# DAC_8CH.net
KiCad netlist of a schematic drawn in Altium Designer
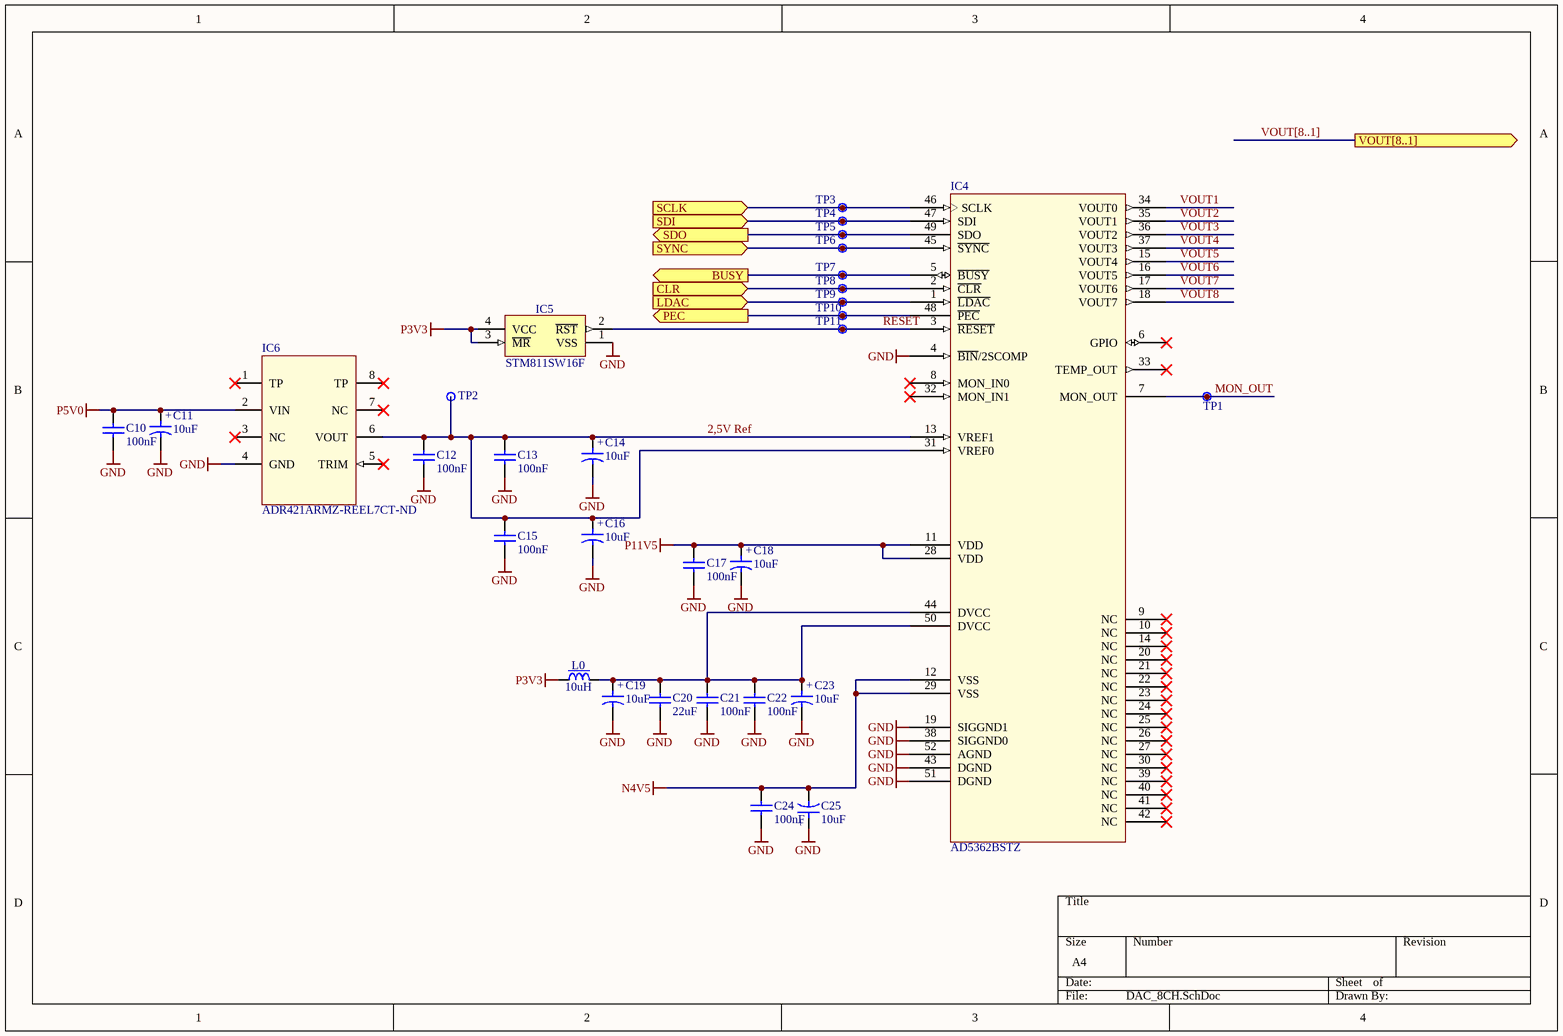
[diagram p0: DAC_8CH.SchDoc]

(export (version "E")
  (design (tool "Eeschema 10.0.6"))
  (components
    (comp (ref "C10")
      (value "100nF")
      (footprint "C0402C104K4RACTU")
      (description "Capacitor; Ceramic; Cap; .100uF; Tol 10%; SMT; Vol-Rtg 16V; X7R; Tape and Reel")
      (fields (field (name "TOLERANCE") "10%"))
      (libsource (lib "CapacitorLibrary") (part "C0402C104K4RACTU"))
    )
    (comp (ref "C11")
      (value "10uF")
      (footprint "TCJT106M016R0200")
      (description "CAP TANT POLY 10UF 16V 1210")
      (fields (field (name "TOLERANCE") "20%") (field (name "VOLTAGE") "16V"))
      (libsource (lib "CapacitorLibrary") (part "TCJT106M016R0200"))
    )
    (comp (ref "C12")
      (value "100nF")
      (footprint "C0402C104K4RACTU")
      (description "Capacitor; Ceramic; Cap; .100uF; Tol 10%; SMT; Vol-Rtg 16V; X7R; Tape and Reel")
      (fields (field (name "TOLERANCE") "10%"))
      (libsource (lib "CapacitorLibrary") (part "C0402C104K4RACTU"))
    )
    (comp (ref "C13")
      (value "100nF")
      (footprint "C0402C104K4RACTU")
      (description "Capacitor; Ceramic; Cap; .100uF; Tol 10%; SMT; Vol-Rtg 16V; X7R; Tape and Reel")
      (fields (field (name "TOLERANCE") "10%"))
      (libsource (lib "CapacitorLibrary") (part "C0402C104K4RACTU"))
    )
    (comp (ref "C14")
      (value "10uF")
      (footprint "TCJT106M016R0200")
      (description "CAP TANT POLY 10UF 16V 1210")
      (fields (field (name "TOLERANCE") "20%") (field (name "VOLTAGE") "16V"))
      (libsource (lib "CapacitorLibrary") (part "TCJT106M016R0200"))
    )
    (comp (ref "C15")
      (value "100nF")
      (footprint "C0402C104K4RACTU")
      (description "Capacitor; Ceramic; Cap; .100uF; Tol 10%; SMT; Vol-Rtg 16V; X7R; Tape and Reel")
      (fields (field (name "TOLERANCE") "10%"))
      (libsource (lib "CapacitorLibrary") (part "C0402C104K4RACTU"))
    )
    (comp (ref "C16")
      (value "10uF")
      (footprint "TCJT106M016R0200")
      (description "CAP TANT POLY 10UF 16V 1210")
      (fields (field (name "TOLERANCE") "20%") (field (name "VOLTAGE") "16V"))
      (libsource (lib "CapacitorLibrary") (part "TCJT106M016R0200"))
    )
    (comp (ref "C17")
      (value "100nF")
      (footprint "C0402C104K4RACTU")
      (description "Capacitor; Ceramic; Cap; .100uF; Tol 10%; SMT; Vol-Rtg 16V; X7R; Tape and Reel")
      (fields (field (name "TOLERANCE") "10%"))
      (libsource (lib "CapacitorLibrary") (part "C0402C104K4RACTU"))
    )
    (comp (ref "C18")
      (value "10uF")
      (footprint "TCJT106M016R0200")
      (description "CAP TANT POLY 10UF 16V 1210")
      (fields (field (name "TOLERANCE") "20%") (field (name "VOLTAGE") "16V"))
      (libsource (lib "CapacitorLibrary") (part "TCJT106M016R0200"))
    )
    (comp (ref "C19")
      (value "10uF")
      (footprint "TCJT106M016R0200")
      (description "CAP TANT POLY 10UF 16V 1210")
      (fields (field (name "TOLERANCE") "20%") (field (name "VOLTAGE") "16V"))
      (libsource (lib "CapacitorLibrary") (part "TCJT106M016R0200"))
    )
    (comp (ref "C20")
      (value "22uF")
      (footprint "GRM219R61C226ME15K")
      (description "CAP CER 22uF 16V X5R 20% SMD 0805 85°C Embossed T/R")
      (fields (field (name "TOLERANCE") "20%"))
      (libsource (lib "CapacitorLibrary") (part "GRM219R61C226ME15K"))
    )
    (comp (ref "C21")
      (value "100nF")
      (footprint "C0402C104K4RACTU")
      (description "Capacitor; Ceramic; Cap; .100uF; Tol 10%; SMT; Vol-Rtg 16V; X7R; Tape and Reel")
      (fields (field (name "TOLERANCE") "10%"))
      (libsource (lib "CapacitorLibrary") (part "C0402C104K4RACTU"))
    )
    (comp (ref "C22")
      (value "100nF")
      (footprint "C0402C104K4RACTU")
      (description "Capacitor; Ceramic; Cap; .100uF; Tol 10%; SMT; Vol-Rtg 16V; X7R; Tape and Reel")
      (fields (field (name "TOLERANCE") "10%"))
      (libsource (lib "CapacitorLibrary") (part "C0402C104K4RACTU"))
    )
    (comp (ref "C23")
      (value "10uF")
      (footprint "TCJT106M016R0200")
      (description "CAP TANT POLY 10UF 16V 1210")
      (fields (field (name "TOLERANCE") "20%") (field (name "VOLTAGE") "16V"))
      (libsource (lib "CapacitorLibrary") (part "TCJT106M016R0200"))
    )
    (comp (ref "C24")
      (value "100nF")
      (footprint "C0402C104K4RACTU")
      (description "Capacitor; Ceramic; Cap; .100uF; Tol 10%; SMT; Vol-Rtg 16V; X7R; Tape and Reel")
      (fields (field (name "TOLERANCE") "10%"))
      (libsource (lib "CapacitorLibrary") (part "C0402C104K4RACTU"))
    )
    (comp (ref "C25")
      (value "10uF")
      (footprint "TCJT106M016R0200")
      (description "CAP TANT POLY 10UF 16V 1210")
      (fields (field (name "TOLERANCE") "20%") (field (name "VOLTAGE") "16V"))
      (libsource (lib "CapacitorLibrary") (part "TCJT106M016R0200"))
    )
    (comp (ref "IC4")
      (value "AD5362BSTZ")
      (footprint "ST-52_L")
      (description "IC, 16BIT DAC, 8CH, SERIAL, 52LFCSP")
      (libsource (lib "InzLib") (part "AD5362BSTZ"))
    )
    (comp (ref "IC5")
      (value "STM811SW16F")
      (footprint "SOT143N")
      (description "Microprocessor Reset Circuit")
      (fields (field (name "MANUFACTURER") "ST MICROELECTRONICS") (field (name "AUTHOR") "CERN DEM JLC"))
      (libsource (lib "ICs And Semiconductors") (part "STM811"))
    )
    (comp (ref "IC6")
      (value "ADR421ARMZ-REEL7")
      (footprint "ADI-RM-8_N")
      (description "V-Ref Precision 2.5V 10mA 8-Pin MSOP T/R")
      (fields
        (field (name "TOLERANCE") "0.12%")
        (field (name "SUPPLIER PART NUMBER 1") "ADR421ARMZ-REEL7CT-ND")
      )
      (libsource (lib "InzLib") (part "ADR421ARMZ-REEL7"))
    )
    (comp (ref "L0")
      (value "10uH")
      (footprint "IND_MURATA-PS_8400")
      (description "Inductor With Core")
      (fields
        (field (name "PART NUMBER") "IND_10UH_10%_MURATA-PS_8400")
        (field (name "POWER") "950mA")
        (field (name "AUTHOR") "CERN DEM JLC")
      )
      (libsource (lib "Inductors & Transformers") (part "Inductor With Magnetic core"))
    )
    (comp (ref "TP1")
      (value "Test Point")
      (footprint "TPS127")
      (fields (field (name "PART NUMBER") "SMD_PAD_1.27X1.27MM") (field (name "AUTHOR") "CERN DEM JLC"))
      (libsource (lib "Eletro-mechanical") (part "Test Point"))
    )
    (comp (ref "TP2")
      (value "Test Point")
      (footprint "TPS127")
      (fields (field (name "PART NUMBER") "SMD_PAD_1.27X1.27MM") (field (name "AUTHOR") "CERN DEM JLC"))
      (libsource (lib "Eletro-mechanical") (part "Test Point"))
    )
    (comp (ref "TP3")
      (value "Test Point")
      (footprint "TPS127")
      (fields (field (name "PART NUMBER") "SMD_PAD_1.27X1.27MM") (field (name "AUTHOR") "CERN DEM JLC"))
      (libsource (lib "Eletro-mechanical") (part "Test Point"))
    )
    (comp (ref "TP4")
      (value "Test Point")
      (footprint "TPS127")
      (fields (field (name "PART NUMBER") "SMD_PAD_1.27X1.27MM") (field (name "AUTHOR") "CERN DEM JLC"))
      (libsource (lib "Eletro-mechanical") (part "Test Point"))
    )
    (comp (ref "TP5")
      (value "Test Point")
      (footprint "TPS127")
      (fields (field (name "PART NUMBER") "SMD_PAD_1.27X1.27MM") (field (name "AUTHOR") "CERN DEM JLC"))
      (libsource (lib "Eletro-mechanical") (part "Test Point"))
    )
    (comp (ref "TP6")
      (value "Test Point")
      (footprint "TPS127")
      (fields (field (name "PART NUMBER") "SMD_PAD_1.27X1.27MM") (field (name "AUTHOR") "CERN DEM JLC"))
      (libsource (lib "Eletro-mechanical") (part "Test Point"))
    )
    (comp (ref "TP7")
      (value "Test Point")
      (footprint "TPS127")
      (fields (field (name "PART NUMBER") "SMD_PAD_1.27X1.27MM") (field (name "AUTHOR") "CERN DEM JLC"))
      (libsource (lib "Eletro-mechanical") (part "Test Point"))
    )
    (comp (ref "TP8")
      (value "Test Point")
      (footprint "TPS127")
      (fields (field (name "PART NUMBER") "SMD_PAD_1.27X1.27MM") (field (name "AUTHOR") "CERN DEM JLC"))
      (libsource (lib "Eletro-mechanical") (part "Test Point"))
    )
    (comp (ref "TP9")
      (value "Test Point")
      (footprint "TPS127")
      (fields (field (name "PART NUMBER") "SMD_PAD_1.27X1.27MM") (field (name "AUTHOR") "CERN DEM JLC"))
      (libsource (lib "Eletro-mechanical") (part "Test Point"))
    )
    (comp (ref "TP10")
      (value "Test Point")
      (footprint "TPS127")
      (fields (field (name "PART NUMBER") "SMD_PAD_1.27X1.27MM") (field (name "AUTHOR") "CERN DEM JLC"))
      (libsource (lib "Eletro-mechanical") (part "Test Point"))
    )
    (comp (ref "TP11")
      (value "Test Point")
      (footprint "TPS127")
      (fields (field (name "PART NUMBER") "SMD_PAD_1.27X1.27MM") (field (name "AUTHOR") "CERN DEM JLC"))
      (libsource (lib "Eletro-mechanical") (part "Test Point"))
    )
  )
  (nets
    (net (code "1") (name "/2,5V Ref") (class "Default")
      (node (ref "C12") (pin "2") (pinfunction "2_2") (pintype "passive"))
      (node (ref "C13") (pin "2") (pinfunction "2_2") (pintype "passive"))
      (node (ref "C14") (pin "1") (pinfunction "1_1") (pintype "passive"))
      (node (ref "C15") (pin "2") (pinfunction "2_2") (pintype "passive"))
      (node (ref "C16") (pin "1") (pinfunction "1_1") (pintype "passive"))
      (node (ref "IC4") (pin "13") (pinfunction "VREF1_13") (pintype "input"))
      (node (ref "IC4") (pin "31") (pinfunction "VREF0_31") (pintype "input"))
      (node (ref "IC6") (pin "6") (pinfunction "VOUT_6") (pintype "power_in"))
      (node (ref "TP2") (pin "1") (pinfunction "1_1") (pintype "bidirectional"))
    )
    (net (code "2") (name "/BUSY") (class "Default")
      (node (ref "IC4") (pin "5") (pinfunction "~{BUSY}_5") (pintype "bidirectional"))
      (node (ref "TP7") (pin "1") (pinfunction "1_1") (pintype "bidirectional"))
    )
    (net (code "3") (name "/CLR") (class "Default")
      (node (ref "IC4") (pin "2") (pinfunction "~{CLR}_2") (pintype "input"))
      (node (ref "TP8") (pin "1") (pinfunction "1_1") (pintype "bidirectional"))
    )
    (net (code "4") (name "/LDAC") (class "Default")
      (node (ref "IC4") (pin "1") (pinfunction "~{LDAC}_1") (pintype "input"))
      (node (ref "TP9") (pin "1") (pinfunction "1_1") (pintype "bidirectional"))
    )
    (net (code "5") (name "/MON_OUT") (class "Default")
      (node (ref "IC4") (pin "7") (pinfunction "MON_OUT_7") (pintype "tri_state"))
      (node (ref "TP1") (pin "1") (pinfunction "1_1") (pintype "bidirectional"))
    )
    (net (code "6") (name "/PEC") (class "Default")
      (node (ref "IC4") (pin "48") (pinfunction "~{PEC}_48") (pintype "open_collector"))
      (node (ref "TP10") (pin "1") (pinfunction "1_1") (pintype "bidirectional"))
    )
    (net (code "7") (name "/SCLK") (class "Default")
      (node (ref "IC4") (pin "46") (pinfunction "SCLK_46") (pintype "input"))
      (node (ref "TP3") (pin "1") (pinfunction "1_1") (pintype "bidirectional"))
    )
    (net (code "8") (name "/SDI") (class "Default")
      (node (ref "IC4") (pin "47") (pinfunction "SDI_47") (pintype "input"))
      (node (ref "TP4") (pin "1") (pinfunction "1_1") (pintype "bidirectional"))
    )
    (net (code "9") (name "/SDO") (class "Default")
      (node (ref "IC4") (pin "49") (pinfunction "SDO_49") (pintype "tri_state"))
      (node (ref "TP5") (pin "1") (pinfunction "1_1") (pintype "bidirectional"))
    )
    (net (code "10") (name "/SYNC") (class "Default")
      (node (ref "IC4") (pin "45") (pinfunction "~{SYNC}_45") (pintype "input"))
      (node (ref "TP6") (pin "1") (pinfunction "1_1") (pintype "bidirectional"))
    )
    (net (code "11") (name "/VOUT1") (class "Default")
      (node (ref "IC4") (pin "34") (pinfunction "VOUT0_34") (pintype "output"))
    )
    (net (code "12") (name "/VOUT2") (class "Default")
      (node (ref "IC4") (pin "35") (pinfunction "VOUT1_35") (pintype "output"))
    )
    (net (code "13") (name "/VOUT3") (class "Default")
      (node (ref "IC4") (pin "36") (pinfunction "VOUT2_36") (pintype "output"))
    )
    (net (code "14") (name "/VOUT4") (class "Default")
      (node (ref "IC4") (pin "37") (pinfunction "VOUT3_37") (pintype "output"))
    )
    (net (code "15") (name "/VOUT5") (class "Default")
      (node (ref "IC4") (pin "15") (pinfunction "VOUT4_15") (pintype "output"))
    )
    (net (code "16") (name "/VOUT6") (class "Default")
      (node (ref "IC4") (pin "16") (pinfunction "VOUT5_16") (pintype "output"))
    )
    (net (code "17") (name "/VOUT7") (class "Default")
      (node (ref "IC4") (pin "17") (pinfunction "VOUT6_17") (pintype "output"))
    )
    (net (code "18") (name "/VOUT8") (class "Default")
      (node (ref "IC4") (pin "18") (pinfunction "VOUT7_18") (pintype "output"))
    )
    (net (code "20") (name "/~{RESET}") (class "Default")
      (node (ref "IC4") (pin "3") (pinfunction "~{RESET}_3") (pintype "input"))
      (node (ref "IC5") (pin "2") (pinfunction "~{RST}_2") (pintype "output"))
      (node (ref "TP11") (pin "1") (pinfunction "1_1") (pintype "bidirectional"))
    )
    (net (code "21") (name "GND") (class "Default")
      (node (ref "C10") (pin "1") (pinfunction "1_1") (pintype "passive"))
      (node (ref "C11") (pin "2") (pinfunction "2_2") (pintype "passive"))
      (node (ref "C12") (pin "1") (pinfunction "1_1") (pintype "passive"))
      (node (ref "C13") (pin "1") (pinfunction "1_1") (pintype "passive"))
      (node (ref "C14") (pin "2") (pinfunction "2_2") (pintype "passive"))
      (node (ref "C15") (pin "1") (pinfunction "1_1") (pintype "passive"))
      (node (ref "C16") (pin "2") (pinfunction "2_2") (pintype "passive"))
      (node (ref "C17") (pin "1") (pinfunction "1_1") (pintype "passive"))
      (node (ref "C18") (pin "2") (pinfunction "2_2") (pintype "passive"))
      (node (ref "C19") (pin "2") (pinfunction "2_2") (pintype "passive"))
      (node (ref "C20") (pin "1") (pinfunction "1_1") (pintype "passive"))
      (node (ref "C21") (pin "1") (pinfunction "1_1") (pintype "passive"))
      (node (ref "C22") (pin "1") (pinfunction "1_1") (pintype "passive"))
      (node (ref "C23") (pin "2") (pinfunction "2_2") (pintype "passive"))
      (node (ref "C24") (pin "1") (pinfunction "1_1") (pintype "passive"))
      (node (ref "C25") (pin "1") (pinfunction "1_1") (pintype "passive"))
      (node (ref "IC4") (pin "19") (pinfunction "SIGGND1_19") (pintype "power_in"))
      (node (ref "IC4") (pin "38") (pinfunction "SIGGND0_38") (pintype "power_in"))
      (node (ref "IC4") (pin "4") (pinfunction "~{BIN}/2SCOMP_4") (pintype "input"))
      (node (ref "IC4") (pin "43") (pinfunction "DGND_43") (pintype "power_in"))
      (node (ref "IC4") (pin "51") (pinfunction "DGND_51") (pintype "power_in"))
      (node (ref "IC4") (pin "52") (pinfunction "AGND_52") (pintype "power_in"))
      (node (ref "IC5") (pin "1") (pinfunction "VSS_1") (pintype "power_in"))
      (node (ref "IC6") (pin "4") (pinfunction "GND_4") (pintype "power_in"))
    )
    (net (code "22") (name "N4V5") (class "Default")
      (node (ref "C24") (pin "2") (pinfunction "2_2") (pintype "passive"))
      (node (ref "C25") (pin "2") (pinfunction "2_2") (pintype "passive"))
      (node (ref "IC4") (pin "12") (pinfunction "VSS_12") (pintype "power_in"))
      (node (ref "IC4") (pin "29") (pinfunction "VSS_29") (pintype "power_in"))
    )
    (net (code "23") (name "Net-(C19-Pad1)") (class "Default")
      (node (ref "C19") (pin "1") (pinfunction "1_1") (pintype "passive"))
      (node (ref "C20") (pin "2") (pinfunction "2_2") (pintype "passive"))
      (node (ref "C21") (pin "2") (pinfunction "2_2") (pintype "passive"))
      (node (ref "C22") (pin "2") (pinfunction "2_2") (pintype "passive"))
      (node (ref "C23") (pin "1") (pinfunction "1_1") (pintype "passive"))
      (node (ref "IC4") (pin "44") (pinfunction "DVCC_44") (pintype "power_in"))
      (node (ref "IC4") (pin "50") (pinfunction "DVCC_50") (pintype "power_in"))
      (node (ref "L0") (pin "2") (pinfunction "2_2") (pintype "passive"))
    )
    (net (code "24") (name "P3V3") (class "Default")
      (node (ref "IC5") (pin "3") (pinfunction "~{MR}_3") (pintype "input"))
      (node (ref "IC5") (pin "4") (pinfunction "VCC_4") (pintype "power_in"))
      (node (ref "L0") (pin "1") (pinfunction "1_1") (pintype "passive"))
    )
    (net (code "25") (name "P5V0") (class "Default")
      (node (ref "C10") (pin "2") (pinfunction "2_2") (pintype "passive"))
      (node (ref "C11") (pin "1") (pinfunction "1_1") (pintype "passive"))
      (node (ref "IC6") (pin "2") (pinfunction "VIN_2") (pintype "power_in"))
    )
    (net (code "26") (name "P11V5") (class "Default")
      (node (ref "C17") (pin "2") (pinfunction "2_2") (pintype "passive"))
      (node (ref "C18") (pin "1") (pinfunction "1_1") (pintype "passive"))
      (node (ref "IC4") (pin "11") (pinfunction "VDD_11") (pintype "power_in"))
      (node (ref "IC4") (pin "28") (pinfunction "VDD_28") (pintype "power_in"))
    )
    (net (code "27") (name "unconnected-(IC4-GPIO-Pad6)") (class "Default")
      (node (ref "IC4") (pin "6") (pinfunction "GPIO_6") (pintype "bidirectional+no_connect"))
    )
    (net (code "28") (name "unconnected-(IC4-MON_IN0-Pad8)") (class "Default")
      (node (ref "IC4") (pin "8") (pinfunction "MON_IN0_8") (pintype "input+no_connect"))
    )
    (net (code "29") (name "unconnected-(IC4-MON_IN1-Pad32)") (class "Default")
      (node (ref "IC4") (pin "32") (pinfunction "MON_IN1_32") (pintype "input+no_connect"))
    )
    (net (code "30") (name "unconnected-(IC4-NC-Pad9)") (class "Default")
      (node (ref "IC4") (pin "9") (pinfunction "NC_9") (pintype "passive+no_connect"))
    )
    (net (code "31") (name "unconnected-(IC4-NC-Pad10)") (class "Default")
      (node (ref "IC4") (pin "10") (pinfunction "NC_10") (pintype "passive+no_connect"))
    )
    (net (code "32") (name "unconnected-(IC4-NC-Pad14)") (class "Default")
      (node (ref "IC4") (pin "14") (pinfunction "NC_14") (pintype "passive+no_connect"))
    )
    (net (code "33") (name "unconnected-(IC4-NC-Pad20)") (class "Default")
      (node (ref "IC4") (pin "20") (pinfunction "NC_20") (pintype "passive+no_connect"))
    )
    (net (code "34") (name "unconnected-(IC4-NC-Pad21)") (class "Default")
      (node (ref "IC4") (pin "21") (pinfunction "NC_21") (pintype "passive+no_connect"))
    )
    (net (code "35") (name "unconnected-(IC4-NC-Pad22)") (class "Default")
      (node (ref "IC4") (pin "22") (pinfunction "NC_22") (pintype "passive+no_connect"))
    )
    (net (code "36") (name "unconnected-(IC4-NC-Pad23)") (class "Default")
      (node (ref "IC4") (pin "23") (pinfunction "NC_23") (pintype "passive+no_connect"))
    )
    (net (code "37") (name "unconnected-(IC4-NC-Pad24)") (class "Default")
      (node (ref "IC4") (pin "24") (pinfunction "NC_24") (pintype "passive+no_connect"))
    )
    (net (code "38") (name "unconnected-(IC4-NC-Pad25)") (class "Default")
      (node (ref "IC4") (pin "25") (pinfunction "NC_25") (pintype "passive+no_connect"))
    )
    (net (code "39") (name "unconnected-(IC4-NC-Pad26)") (class "Default")
      (node (ref "IC4") (pin "26") (pinfunction "NC_26") (pintype "passive+no_connect"))
    )
    (net (code "40") (name "unconnected-(IC4-NC-Pad27)") (class "Default")
      (node (ref "IC4") (pin "27") (pinfunction "NC_27") (pintype "passive+no_connect"))
    )
    (net (code "41") (name "unconnected-(IC4-NC-Pad30)") (class "Default")
      (node (ref "IC4") (pin "30") (pinfunction "NC_30") (pintype "passive+no_connect"))
    )
    (net (code "42") (name "unconnected-(IC4-NC-Pad39)") (class "Default")
      (node (ref "IC4") (pin "39") (pinfunction "NC_39") (pintype "passive+no_connect"))
    )
    (net (code "43") (name "unconnected-(IC4-NC-Pad40)") (class "Default")
      (node (ref "IC4") (pin "40") (pinfunction "NC_40") (pintype "passive+no_connect"))
    )
    (net (code "44") (name "unconnected-(IC4-NC-Pad41)") (class "Default")
      (node (ref "IC4") (pin "41") (pinfunction "NC_41") (pintype "passive+no_connect"))
    )
    (net (code "45") (name "unconnected-(IC4-NC-Pad42)") (class "Default")
      (node (ref "IC4") (pin "42") (pinfunction "NC_42") (pintype "passive+no_connect"))
    )
    (net (code "46") (name "unconnected-(IC4-TEMP_OUT-Pad33)") (class "Default")
      (node (ref "IC4") (pin "33") (pinfunction "TEMP_OUT_33") (pintype "output+no_connect"))
    )
    (net (code "47") (name "unconnected-(IC6-NC-Pad3)") (class "Default")
      (node (ref "IC6") (pin "3") (pinfunction "NC_3") (pintype "passive+no_connect"))
    )
    (net (code "48") (name "unconnected-(IC6-NC-Pad7)") (class "Default")
      (node (ref "IC6") (pin "7") (pinfunction "NC_7") (pintype "passive+no_connect"))
    )
    (net (code "49") (name "unconnected-(IC6-TP-Pad1)") (class "Default")
      (node (ref "IC6") (pin "1") (pinfunction "TP_1") (pintype "passive+no_connect"))
    )
    (net (code "50") (name "unconnected-(IC6-TP-Pad8)") (class "Default")
      (node (ref "IC6") (pin "8") (pinfunction "TP_8") (pintype "passive+no_connect"))
    )
    (net (code "51") (name "unconnected-(IC6-TRIM-Pad5)") (class "Default")
      (node (ref "IC6") (pin "5") (pinfunction "TRIM_5") (pintype "input+no_connect"))
    )
  )
)
